# zb_pt4115_v1_2.net
KiCad netlist of a schematic drawn in EAGLE
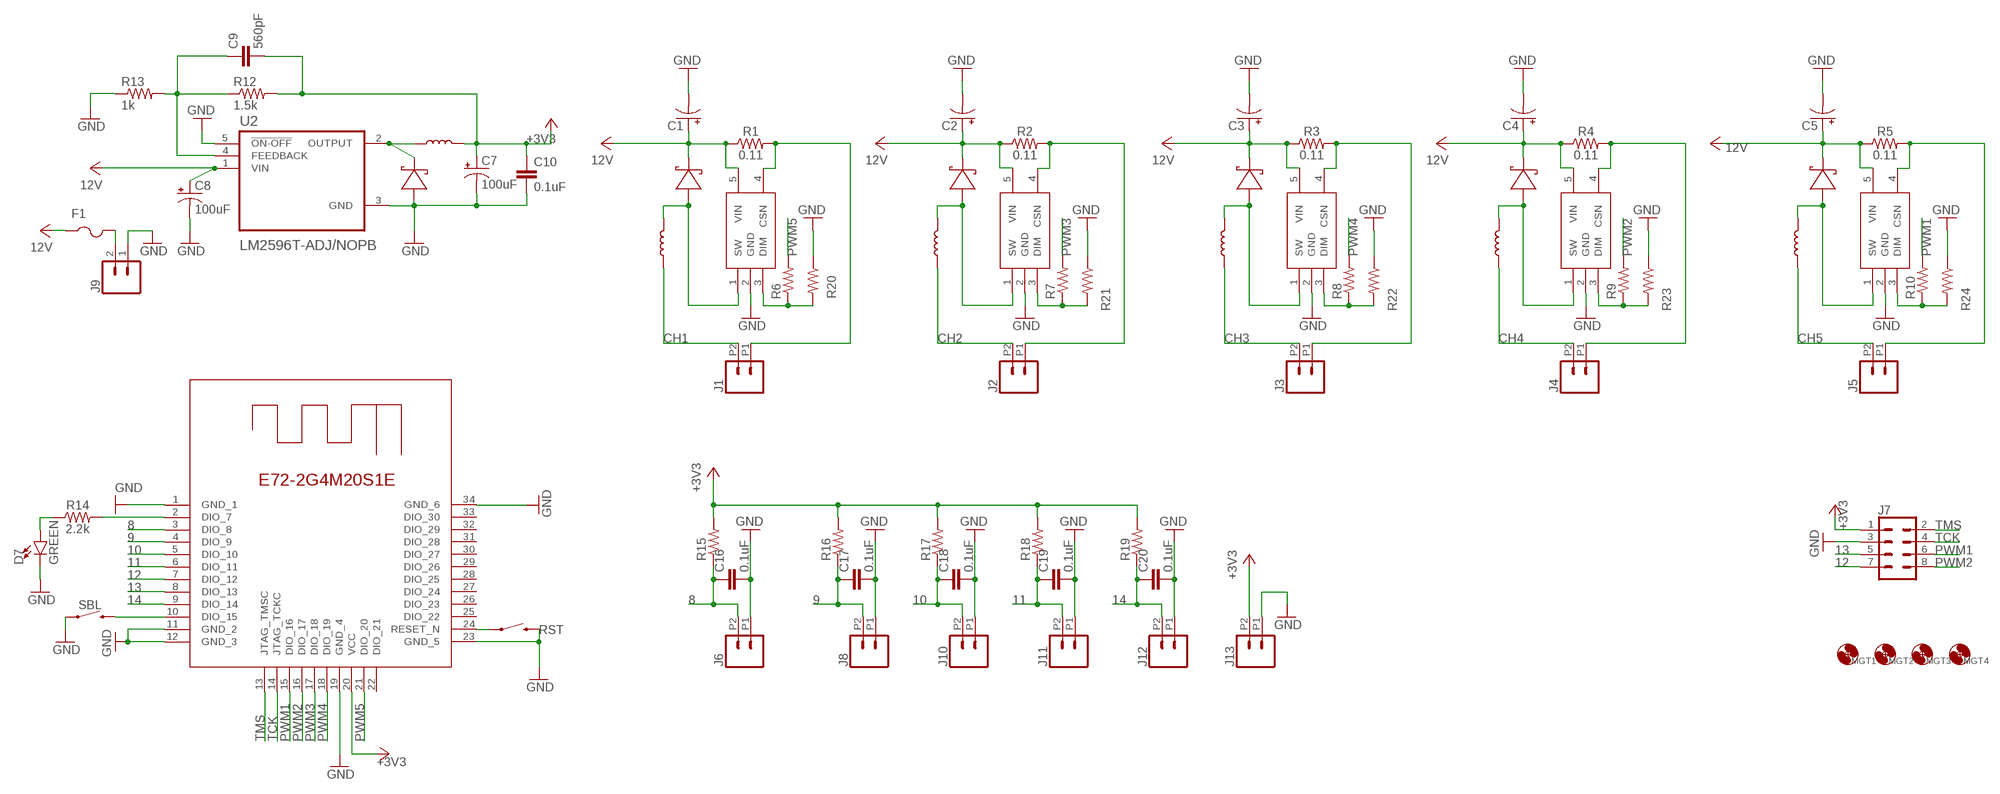
[diagram p0: schematic, sheet 1]

(export (version "E")
  (design (tool "Eeschema 10.0.6"))
  (components
    (comp (ref "C1")
      (value "100uF")
      (footprint "eagle-import:EIA7343")
      (libsource (lib "eagle-import") (part "100UF-POLAR-EIA7343-16V-10%(TANT)"))
    )
    (comp (ref "C2")
      (value "100uF")
      (footprint "eagle-import:EIA7343")
      (libsource (lib "eagle-import") (part "100UF-POLAR-EIA7343-16V-10%(TANT)"))
    )
    (comp (ref "C3")
      (value "100uF")
      (footprint "eagle-import:EIA7343")
      (libsource (lib "eagle-import") (part "100UF-POLAR-EIA7343-16V-10%(TANT)"))
    )
    (comp (ref "C4")
      (value "100uF")
      (footprint "eagle-import:EIA7343")
      (libsource (lib "eagle-import") (part "100UF-POLAR-EIA7343-16V-10%(TANT)"))
    )
    (comp (ref "C5")
      (value "100uF")
      (footprint "eagle-import:EIA7343")
      (libsource (lib "eagle-import") (part "100UF-POLAR-EIA7343-16V-10%(TANT)"))
    )
    (comp (ref "C7")
      (value "100uF")
      (footprint "eagle-import:PANASONIC_D")
      (libsource (lib "eagle-import") (part "SparkFun-Capacitors_510_100UF-POLAR-25V-20%(ELEC)"))
    )
    (comp (ref "C8")
      (value "100uF")
      (footprint "eagle-import:PANASONIC_D")
      (libsource (lib "eagle-import") (part "SparkFun-Capacitors_510_100UF-POLAR-25V-20%(ELEC)"))
    )
    (comp (ref "C9")
      (value "560pF")
      (footprint "eagle-import:0603")
      (libsource (lib "eagle-import") (part "560PF-0603-50V-5%"))
    )
    (comp (ref "C10")
      (value "0.1uF")
      (footprint "eagle-import:0603")
      (libsource (lib "eagle-import") (part "0.1UF-0603-25V-5%"))
    )
    (comp (ref "C16")
      (value "0.1uF")
      (footprint "eagle-import:0603")
      (libsource (lib "eagle-import") (part "0.1UF-0603-100V-10%"))
    )
    (comp (ref "C17")
      (value "0.1uF")
      (footprint "eagle-import:0603")
      (libsource (lib "eagle-import") (part "0.1UF-0603-100V-10%"))
    )
    (comp (ref "C18")
      (value "0.1uF")
      (footprint "eagle-import:0603")
      (libsource (lib "eagle-import") (part "0.1UF-0603-100V-10%"))
    )
    (comp (ref "C19")
      (value "0.1uF")
      (footprint "eagle-import:0603")
      (libsource (lib "eagle-import") (part "0.1UF-0603-100V-10%"))
    )
    (comp (ref "C20")
      (value "0.1uF")
      (footprint "eagle-import:0603")
      (libsource (lib "eagle-import") (part "0.1UF-0603-100V-10%"))
    )
    (comp (ref "D1")
      (value "SS18")
      (footprint "eagle-import:DIOM5227X270N")
      (fields (field (name "MOUSER_PART_NUMBER") "512-SS18"))
      (libsource (lib "eagle-import") (part "SS18"))
    )
    (comp (ref "D2")
      (value "SS18")
      (footprint "eagle-import:DIOM5227X270N")
      (fields (field (name "MOUSER_PART_NUMBER") "512-SS18"))
      (libsource (lib "eagle-import") (part "SS18"))
    )
    (comp (ref "D3")
      (value "SS18")
      (footprint "eagle-import:DIOM5227X270N")
      (fields (field (name "MOUSER_PART_NUMBER") "512-SS18"))
      (libsource (lib "eagle-import") (part "SS18"))
    )
    (comp (ref "D4")
      (value "SS18")
      (footprint "eagle-import:DIOM5227X270N")
      (fields (field (name "MOUSER_PART_NUMBER") "512-SS18"))
      (libsource (lib "eagle-import") (part "SS18"))
    )
    (comp (ref "D5")
      (value "SS18")
      (footprint "eagle-import:DIOM5227X270N")
      (fields (field (name "MOUSER_PART_NUMBER") "512-SS18"))
      (libsource (lib "eagle-import") (part "SS18"))
    )
    (comp (ref "D6")
      (value "SS18")
      (footprint "eagle-import:DIOM5227X270N")
      (fields (field (name "MOUSER_PART_NUMBER") "512-SS18"))
      (libsource (lib "eagle-import") (part "SS18"))
    )
    (comp (ref "D7")
      (value "GREEN")
      (footprint "eagle-import:LED-0603")
      (libsource (lib "eagle-import") (part "LED-GREEN0603"))
    )
    (comp (ref "F1")
      (value "PTCFUSE-1812")
      (footprint "eagle-import:1812")
      (libsource (lib "eagle-import") (part "PTCFUSE-1812"))
    )
    (comp (ref "IC1")
      (value "68uH")
      (footprint "eagle-import:INDPM102100X400N")
      (fields
        (field (name "MANUFACTURER_PART_NUMBER") "MSS1038-473MLB")
        (field (name "MOUSER_PART_NUMBER") "994-MSS1038-473MLB")
      )
      (libsource (lib "eagle-import") (part "MSS1038-473MLB"))
    )
    (comp (ref "IC2")
      (value "68uH")
      (footprint "eagle-import:INDPM102100X400N")
      (fields
        (field (name "MANUFACTURER_PART_NUMBER") "MSS1038-473MLB")
        (field (name "MOUSER_PART_NUMBER") "994-MSS1038-473MLB")
      )
      (libsource (lib "eagle-import") (part "MSS1038-473MLB"))
    )
    (comp (ref "IC3")
      (value "68uH")
      (footprint "eagle-import:INDPM102100X400N")
      (fields
        (field (name "MANUFACTURER_PART_NUMBER") "MSS1038-473MLB")
        (field (name "MOUSER_PART_NUMBER") "994-MSS1038-473MLB")
      )
      (libsource (lib "eagle-import") (part "MSS1038-473MLB"))
    )
    (comp (ref "IC4")
      (value "68uH")
      (footprint "eagle-import:INDPM102100X400N")
      (fields
        (field (name "MANUFACTURER_PART_NUMBER") "MSS1038-473MLB")
        (field (name "MOUSER_PART_NUMBER") "994-MSS1038-473MLB")
      )
      (libsource (lib "eagle-import") (part "MSS1038-473MLB"))
    )
    (comp (ref "IC5")
      (value "68uH")
      (footprint "eagle-import:INDPM102100X400N")
      (fields
        (field (name "MANUFACTURER_PART_NUMBER") "MSS1038-473MLB")
        (field (name "MOUSER_PART_NUMBER") "994-MSS1038-473MLB")
      )
      (libsource (lib "eagle-import") (part "MSS1038-473MLB"))
    )
    (comp (ref "IC6")
      (value "68uH")
      (footprint "eagle-import:INDPM102100X400N")
      (fields
        (field (name "MANUFACTURER_PART_NUMBER") "MSS1038-473MLB")
        (field (name "MOUSER_PART_NUMBER") "994-MSS1038-473MLB")
      )
      (libsource (lib "eagle-import") (part "MSS1038-473MLB"))
    )
    (comp (ref "J1")
      (value "CONN_022.54MM_SCREWTERM")
      (footprint "eagle-import:1X02_2.54_SCREWTERM")
      (libsource (lib "eagle-import") (part "CONN_022.54MM_SCREWTERM"))
    )
    (comp (ref "J2")
      (value "CONN_022.54MM_SCREWTERM")
      (footprint "eagle-import:1X02_2.54_SCREWTERM")
      (libsource (lib "eagle-import") (part "CONN_022.54MM_SCREWTERM"))
    )
    (comp (ref "J3")
      (value "CONN_022.54MM_SCREWTERM")
      (footprint "eagle-import:1X02_2.54_SCREWTERM")
      (libsource (lib "eagle-import") (part "CONN_022.54MM_SCREWTERM"))
    )
    (comp (ref "J4")
      (value "CONN_022.54MM_SCREWTERM")
      (footprint "eagle-import:1X02_2.54_SCREWTERM")
      (libsource (lib "eagle-import") (part "CONN_022.54MM_SCREWTERM"))
    )
    (comp (ref "J5")
      (value "CONN_022.54MM_SCREWTERM")
      (footprint "eagle-import:1X02_2.54_SCREWTERM")
      (libsource (lib "eagle-import") (part "CONN_022.54MM_SCREWTERM"))
    )
    (comp (ref "J6")
      (value "CONN_022.54MM_SCREWTERM")
      (footprint "eagle-import:1X02_2.54_SCREWTERM")
      (libsource (lib "eagle-import") (part "CONN_022.54MM_SCREWTERM"))
    )
    (comp (ref "J7")
      (value "CONN_04X2")
      (footprint "eagle-import:2X4")
      (libsource (lib "eagle-import") (part "CONN_04X2"))
    )
    (comp (ref "J8")
      (value "CONN_022.54MM_SCREWTERM")
      (footprint "eagle-import:1X02_2.54_SCREWTERM")
      (libsource (lib "eagle-import") (part "CONN_022.54MM_SCREWTERM"))
    )
    (comp (ref "J9")
      (value "CONN_025MM")
      (footprint "eagle-import:SCREWTERMINAL-5MM-2")
      (libsource (lib "eagle-import") (part "SparkFun-SEWPAD16_CONN_025MM"))
    )
    (comp (ref "J10")
      (value "CONN_022.54MM_SCREWTERM")
      (footprint "eagle-import:1X02_2.54_SCREWTERM")
      (libsource (lib "eagle-import") (part "CONN_022.54MM_SCREWTERM"))
    )
    (comp (ref "J11")
      (value "CONN_022.54MM_SCREWTERM")
      (footprint "eagle-import:1X02_2.54_SCREWTERM")
      (libsource (lib "eagle-import") (part "CONN_022.54MM_SCREWTERM"))
    )
    (comp (ref "J12")
      (value "CONN_022.54MM_SCREWTERM")
      (footprint "eagle-import:1X02_2.54_SCREWTERM")
      (libsource (lib "eagle-import") (part "CONN_022.54MM_SCREWTERM"))
    )
    (comp (ref "J13")
      (value "CONN_022.54MM_SCREWTERM")
      (footprint "eagle-import:1X02_2.54_SCREWTERM")
      (libsource (lib "eagle-import") (part "CONN_022.54MM_SCREWTERM"))
    )
    (comp (ref "MGT1")
      (value "MOUNT-HOLE3.0")
      (footprint "eagle-import:3,0")
      (libsource (lib "eagle-import") (part "MOUNT-HOLE3.0"))
    )
    (comp (ref "MGT2")
      (value "MOUNT-HOLE3.0")
      (footprint "eagle-import:3,0")
      (libsource (lib "eagle-import") (part "MOUNT-HOLE3.0"))
    )
    (comp (ref "MGT3")
      (value "MOUNT-HOLE3.0")
      (footprint "eagle-import:3,0")
      (libsource (lib "eagle-import") (part "MOUNT-HOLE3.0"))
    )
    (comp (ref "MGT4")
      (value "MOUNT-HOLE3.0")
      (footprint "eagle-import:3,0")
      (libsource (lib "eagle-import") (part "MOUNT-HOLE3.0"))
    )
    (comp (ref "R1")
      (value "0.11")
      (footprint "eagle-import:2010")
      (libsource (lib "eagle-import") (part "0.11OHM-2010-1/2W-1%"))
    )
    (comp (ref "R2")
      (value "0.11")
      (footprint "eagle-import:2010")
      (libsource (lib "eagle-import") (part "0.11OHM-2010-1/2W-1%"))
    )
    (comp (ref "R3")
      (value "0.11")
      (footprint "eagle-import:2010")
      (libsource (lib "eagle-import") (part "0.11OHM-2010-1/2W-1%"))
    )
    (comp (ref "R4")
      (value "0.11")
      (footprint "eagle-import:2010")
      (libsource (lib "eagle-import") (part "0.11OHM-2010-1/2W-1%"))
    )
    (comp (ref "R5")
      (value "0.11")
      (footprint "eagle-import:2010")
      (libsource (lib "eagle-import") (part "0.11OHM-2010-1/2W-1%"))
    )
    (comp (ref "R6")
      (value "100Ohm")
      (footprint "eagle-import:R0805")
      (libsource (lib "eagle-import") (part "R-US_R0805"))
    )
    (comp (ref "R7")
      (value "100Ohm")
      (footprint "eagle-import:R0805")
      (libsource (lib "eagle-import") (part "R-US_R0805"))
    )
    (comp (ref "R8")
      (value "100Ohm")
      (footprint "eagle-import:R0805")
      (libsource (lib "eagle-import") (part "R-US_R0805"))
    )
    (comp (ref "R9")
      (value "100Ohm")
      (footprint "eagle-import:R0805")
      (libsource (lib "eagle-import") (part "R-US_R0805"))
    )
    (comp (ref "R10")
      (value "100Ohm")
      (footprint "eagle-import:R0805")
      (libsource (lib "eagle-import") (part "R-US_R0805"))
    )
    (comp (ref "R12")
      (value "1.5k")
      (footprint "eagle-import:R0805")
      (libsource (lib "eagle-import") (part "R-US_R0805"))
    )
    (comp (ref "R13")
      (value "1k")
      (footprint "eagle-import:R0805")
      (libsource (lib "eagle-import") (part "R-US_R0805"))
    )
    (comp (ref "R14")
      (value "2.2k")
      (footprint "eagle-import:0603")
      (libsource (lib "eagle-import") (part "2.2KOHM-0603-1/10W-1%"))
    )
    (comp (ref "R15")
      (value "10k")
      (footprint "eagle-import:R0805")
      (libsource (lib "eagle-import") (part "R-US_R0805"))
    )
    (comp (ref "R16")
      (value "10k")
      (footprint "eagle-import:R0805")
      (libsource (lib "eagle-import") (part "R-US_R0805"))
    )
    (comp (ref "R17")
      (value "10k")
      (footprint "eagle-import:R0805")
      (libsource (lib "eagle-import") (part "R-US_R0805"))
    )
    (comp (ref "R18")
      (value "10k")
      (footprint "eagle-import:R0805")
      (libsource (lib "eagle-import") (part "R-US_R0805"))
    )
    (comp (ref "R19")
      (value "10k")
      (footprint "eagle-import:R0805")
      (libsource (lib "eagle-import") (part "R-US_R0805"))
    )
    (comp (ref "R20")
      (value "3k")
      (footprint "eagle-import:R0805")
      (libsource (lib "eagle-import") (part "R-US_R0805"))
    )
    (comp (ref "R21")
      (value "3k")
      (footprint "eagle-import:R0805")
      (libsource (lib "eagle-import") (part "R-US_R0805"))
    )
    (comp (ref "R22")
      (value "3k")
      (footprint "eagle-import:R0805")
      (libsource (lib "eagle-import") (part "R-US_R0805"))
    )
    (comp (ref "R23")
      (value "3k")
      (footprint "eagle-import:R0805")
      (libsource (lib "eagle-import") (part "R-US_R0805"))
    )
    (comp (ref "R24")
      (value "3k")
      (footprint "eagle-import:R0805")
      (libsource (lib "eagle-import") (part "R-US_R0805"))
    )
    (comp (ref "RST")
      (value "MOMENTARY-SWITCH-SPST-SMD-4.6X2.8MM")
      (footprint "eagle-import:TACTILE_SWITCH_SMD_4.6X2.8MM")
      (libsource (lib "eagle-import") (part "MOMENTARY-SWITCH-SPST-SMD-4.6X2.8MM"))
    )
    (comp (ref "SBL")
      (value "MOMENTARY-SWITCH-SPST-SMD-4.6X2.8MM")
      (footprint "eagle-import:TACTILE_SWITCH_SMD_4.6X2.8MM")
      (libsource (lib "eagle-import") (part "MOMENTARY-SWITCH-SPST-SMD-4.6X2.8MM"))
    )
    (comp (ref "U$1")
      (value "PT4115")
      (footprint "eagle-import:SOT-89-5")
      (fields (field (name "MF") "Pulse"))
      (libsource (lib "eagle-import") (part "PT4115"))
    )
    (comp (ref "U$2")
      (value "PT4115")
      (footprint "eagle-import:SOT-89-5")
      (fields (field (name "MF") "Pulse"))
      (libsource (lib "eagle-import") (part "PT4115"))
    )
    (comp (ref "U$3")
      (value "PT4115")
      (footprint "eagle-import:SOT-89-5")
      (fields (field (name "MF") "Pulse"))
      (libsource (lib "eagle-import") (part "PT4115"))
    )
    (comp (ref "U$4")
      (value "PT4115")
      (footprint "eagle-import:SOT-89-5")
      (fields (field (name "MF") "Pulse"))
      (libsource (lib "eagle-import") (part "PT4115"))
    )
    (comp (ref "U$5")
      (value "PT4115")
      (footprint "eagle-import:SOT-89-5")
      (fields (field (name "MF") "Pulse"))
      (libsource (lib "eagle-import") (part "PT4115"))
    )
    (comp (ref "U$6")
      (value "E72-2G4M20S1E")
      (footprint "eagle-import:E72-2G4M20S1E")
      (libsource (lib "eagle-import") (part "E72-2G4M20S1E"))
    )
    (comp (ref "U2")
      (value "LM2596T-ADJ/NOPB")
      (footprint "eagle-import:TO170P1016X470X2092-5")
      (fields (field (name "MF") "Texas Instruments"))
      (libsource (lib "eagle-import") (part "LM2596T-ADJ/NOPB"))
    )
  )
  (nets
    (net (code "1") (name "+3V3") (class "Default")
      (node (ref "C10") (pin "1") (pinfunction "1_1") (pintype "passive"))
      (node (ref "C7") (pin "+") (pinfunction "+_+") (pintype "passive"))
      (node (ref "C9") (pin "2") (pinfunction "2_2") (pintype "passive"))
      (node (ref "IC6") (pin "2") (pinfunction "2_2") (pintype "bidirectional"))
      (node (ref "J13") (pin "P2") (pinfunction "2_P2") (pintype "passive"))
      (node (ref "J7") (pin "1") (pinfunction "1_1") (pintype "passive"))
      (node (ref "R12") (pin "2") (pinfunction "2_2") (pintype "passive"))
      (node (ref "R15") (pin "2") (pinfunction "2_2") (pintype "passive"))
      (node (ref "R16") (pin "2") (pinfunction "2_2") (pintype "passive"))
      (node (ref "R17") (pin "2") (pinfunction "2_2") (pintype "passive"))
      (node (ref "R18") (pin "2") (pinfunction "2_2") (pintype "passive"))
      (node (ref "R19") (pin "2") (pinfunction "2_2") (pintype "passive"))
      (node (ref "U$6") (pin "20") (pinfunction "VCC_20") (pintype "bidirectional"))
    )
    (net (code "2") (name "/8") (class "Default")
      (node (ref "C16") (pin "1") (pinfunction "1_1") (pintype "passive"))
      (node (ref "J6") (pin "P2") (pinfunction "2_P2") (pintype "passive"))
      (node (ref "R15") (pin "1") (pinfunction "1_1") (pintype "passive"))
      (node (ref "U$6") (pin "3") (pinfunction "DIO_8_3") (pintype "bidirectional"))
    )
    (net (code "3") (name "/9") (class "Default")
      (node (ref "C17") (pin "1") (pinfunction "1_1") (pintype "passive"))
      (node (ref "J8") (pin "P2") (pinfunction "2_P2") (pintype "passive"))
      (node (ref "R16") (pin "1") (pinfunction "1_1") (pintype "passive"))
      (node (ref "U$6") (pin "4") (pinfunction "DIO_9_4") (pintype "bidirectional"))
    )
    (net (code "4") (name "/10") (class "Default")
      (node (ref "C18") (pin "1") (pinfunction "1_1") (pintype "passive"))
      (node (ref "J10") (pin "P2") (pinfunction "2_P2") (pintype "passive"))
      (node (ref "R17") (pin "1") (pinfunction "1_1") (pintype "passive"))
      (node (ref "U$6") (pin "5") (pinfunction "DIO_10_5") (pintype "bidirectional"))
    )
    (net (code "5") (name "/11") (class "Default")
      (node (ref "C19") (pin "1") (pinfunction "1_1") (pintype "passive"))
      (node (ref "J11") (pin "P2") (pinfunction "2_P2") (pintype "passive"))
      (node (ref "R18") (pin "1") (pinfunction "1_1") (pintype "passive"))
      (node (ref "U$6") (pin "6") (pinfunction "DIO_11_6") (pintype "bidirectional"))
    )
    (net (code "6") (name "/12") (class "Default")
      (node (ref "J7") (pin "7") (pinfunction "7_7") (pintype "passive"))
      (node (ref "U$6") (pin "7") (pinfunction "DIO_12_7") (pintype "bidirectional"))
    )
    (net (code "7") (name "/13") (class "Default")
      (node (ref "J7") (pin "5") (pinfunction "5_5") (pintype "passive"))
      (node (ref "U$6") (pin "8") (pinfunction "DIO_13_8") (pintype "bidirectional"))
    )
    (net (code "8") (name "/14") (class "Default")
      (node (ref "C20") (pin "1") (pinfunction "1_1") (pintype "passive"))
      (node (ref "J12") (pin "P2") (pinfunction "2_P2") (pintype "passive"))
      (node (ref "R19") (pin "1") (pinfunction "1_1") (pintype "passive"))
      (node (ref "U$6") (pin "9") (pinfunction "DIO_14_9") (pintype "bidirectional"))
    )
    (net (code "9") (name "/CH1") (class "Default")
      (node (ref "IC1") (pin "1") (pinfunction "1_1") (pintype "bidirectional"))
      (node (ref "J1") (pin "P2") (pinfunction "2_P2") (pintype "passive"))
    )
    (net (code "10") (name "/CH2") (class "Default")
      (node (ref "IC2") (pin "1") (pinfunction "1_1") (pintype "bidirectional"))
      (node (ref "J2") (pin "P2") (pinfunction "2_P2") (pintype "passive"))
    )
    (net (code "11") (name "/CH3") (class "Default")
      (node (ref "IC3") (pin "1") (pinfunction "1_1") (pintype "bidirectional"))
      (node (ref "J3") (pin "P2") (pinfunction "2_P2") (pintype "passive"))
    )
    (net (code "12") (name "/CH4") (class "Default")
      (node (ref "IC4") (pin "1") (pinfunction "1_1") (pintype "bidirectional"))
      (node (ref "J4") (pin "P2") (pinfunction "2_P2") (pintype "passive"))
    )
    (net (code "13") (name "/CH5") (class "Default")
      (node (ref "IC5") (pin "1") (pinfunction "1_1") (pintype "bidirectional"))
      (node (ref "J5") (pin "P2") (pinfunction "2_P2") (pintype "passive"))
    )
    (net (code "14") (name "/PWM1") (class "Default")
      (node (ref "J7") (pin "6") (pinfunction "6_6") (pintype "passive"))
      (node (ref "R10") (pin "2") (pinfunction "2_2") (pintype "passive"))
      (node (ref "U$6") (pin "15") (pinfunction "DIO_16_15") (pintype "bidirectional"))
    )
    (net (code "15") (name "/PWM2") (class "Default")
      (node (ref "J7") (pin "8") (pinfunction "8_8") (pintype "passive"))
      (node (ref "R9") (pin "2") (pinfunction "2_2") (pintype "passive"))
      (node (ref "U$6") (pin "16") (pinfunction "DIO_17_16") (pintype "bidirectional"))
    )
    (net (code "16") (name "/PWM3") (class "Default")
      (node (ref "R7") (pin "2") (pinfunction "2_2") (pintype "passive"))
      (node (ref "U$6") (pin "17") (pinfunction "DIO_18_17") (pintype "bidirectional"))
    )
    (net (code "17") (name "/PWM4") (class "Default")
      (node (ref "R8") (pin "2") (pinfunction "2_2") (pintype "passive"))
      (node (ref "U$6") (pin "18") (pinfunction "DIO_19_18") (pintype "bidirectional"))
    )
    (net (code "18") (name "/PWM5") (class "Default")
      (node (ref "R6") (pin "2") (pinfunction "2_2") (pintype "passive"))
      (node (ref "U$6") (pin "21") (pinfunction "DIO_20_21") (pintype "bidirectional"))
    )
    (net (code "19") (name "/TCK") (class "Default")
      (node (ref "J7") (pin "4") (pinfunction "4_4") (pintype "passive"))
      (node (ref "U$6") (pin "14") (pinfunction "JTAG_TCKC_14") (pintype "bidirectional"))
    )
    (net (code "20") (name "/TMS") (class "Default")
      (node (ref "J7") (pin "2") (pinfunction "2_2") (pintype "passive"))
      (node (ref "U$6") (pin "13") (pinfunction "JTAG_TMSC_13") (pintype "bidirectional"))
    )
    (net (code "21") (name "12V") (class "Default")
      (node (ref "C1") (pin "A") (pinfunction "+_A") (pintype "passive"))
      (node (ref "C2") (pin "A") (pinfunction "+_A") (pintype "passive"))
      (node (ref "C3") (pin "A") (pinfunction "+_A") (pintype "passive"))
      (node (ref "C4") (pin "A") (pinfunction "+_A") (pintype "passive"))
      (node (ref "C5") (pin "A") (pinfunction "+_A") (pintype "passive"))
      (node (ref "C8") (pin "+") (pinfunction "+_+") (pintype "passive"))
      (node (ref "D1") (pin "1") (pinfunction "K_1") (pintype "bidirectional"))
      (node (ref "D2") (pin "1") (pinfunction "K_1") (pintype "bidirectional"))
      (node (ref "D3") (pin "1") (pinfunction "K_1") (pintype "bidirectional"))
      (node (ref "D4") (pin "1") (pinfunction "K_1") (pintype "bidirectional"))
      (node (ref "D5") (pin "1") (pinfunction "K_1") (pintype "bidirectional"))
      (node (ref "F1") (pin "1") (pinfunction "1_1") (pintype "passive"))
      (node (ref "F1") (pin "2") (pinfunction "2_2") (pintype "passive"))
      (node (ref "J9") (pin "2") (pinfunction "2_2") (pintype "passive"))
      (node (ref "R1") (pin "1") (pinfunction "1_1") (pintype "passive"))
      (node (ref "R2") (pin "1") (pinfunction "1_1") (pintype "passive"))
      (node (ref "R3") (pin "1") (pinfunction "1_1") (pintype "passive"))
      (node (ref "R4") (pin "1") (pinfunction "1_1") (pintype "passive"))
      (node (ref "R5") (pin "1") (pinfunction "1_1") (pintype "passive"))
      (node (ref "U$1") (pin "5") (pinfunction "VIN_5") (pintype "bidirectional"))
      (node (ref "U$2") (pin "5") (pinfunction "VIN_5") (pintype "bidirectional"))
      (node (ref "U$3") (pin "5") (pinfunction "VIN_5") (pintype "bidirectional"))
      (node (ref "U$4") (pin "5") (pinfunction "VIN_5") (pintype "bidirectional"))
      (node (ref "U$5") (pin "5") (pinfunction "VIN_5") (pintype "bidirectional"))
      (node (ref "U2") (pin "1") (pinfunction "VIN_1") (pintype "input"))
    )
    (net (code "22") (name "GND") (class "Default")
      (node (ref "C1") (pin "C") (pinfunction "-_C") (pintype "passive"))
      (node (ref "C10") (pin "2") (pinfunction "2_2") (pintype "passive"))
      (node (ref "C16") (pin "2") (pinfunction "2_2") (pintype "passive"))
      (node (ref "C17") (pin "2") (pinfunction "2_2") (pintype "passive"))
      (node (ref "C18") (pin "2") (pinfunction "2_2") (pintype "passive"))
      (node (ref "C19") (pin "2") (pinfunction "2_2") (pintype "passive"))
      (node (ref "C2") (pin "C") (pinfunction "-_C") (pintype "passive"))
      (node (ref "C20") (pin "2") (pinfunction "2_2") (pintype "passive"))
      (node (ref "C3") (pin "C") (pinfunction "-_C") (pintype "passive"))
      (node (ref "C4") (pin "C") (pinfunction "-_C") (pintype "passive"))
      (node (ref "C5") (pin "C") (pinfunction "-_C") (pintype "passive"))
      (node (ref "C7") (pin "-") (pinfunction "-_-") (pintype "passive"))
      (node (ref "C8") (pin "-") (pinfunction "-_-") (pintype "passive"))
      (node (ref "D6") (pin "2") (pinfunction "A_2") (pintype "bidirectional"))
      (node (ref "D7") (pin "C") (pinfunction "C_C") (pintype "passive"))
      (node (ref "J10") (pin "P1") (pinfunction "1_P1") (pintype "passive"))
      (node (ref "J11") (pin "P1") (pinfunction "1_P1") (pintype "passive"))
      (node (ref "J12") (pin "P1") (pinfunction "1_P1") (pintype "passive"))
      (node (ref "J13") (pin "P1") (pinfunction "1_P1") (pintype "passive"))
      (node (ref "J6") (pin "P1") (pinfunction "1_P1") (pintype "passive"))
      (node (ref "J7") (pin "3") (pinfunction "3_3") (pintype "passive"))
      (node (ref "J8") (pin "P1") (pinfunction "1_P1") (pintype "passive"))
      (node (ref "J9") (pin "1") (pinfunction "1_1") (pintype "passive"))
      (node (ref "R13") (pin "1") (pinfunction "1_1") (pintype "passive"))
      (node (ref "R20") (pin "1") (pinfunction "1_1") (pintype "passive"))
      (node (ref "R21") (pin "1") (pinfunction "1_1") (pintype "passive"))
      (node (ref "R22") (pin "1") (pinfunction "1_1") (pintype "passive"))
      (node (ref "R23") (pin "1") (pinfunction "1_1") (pintype "passive"))
      (node (ref "R24") (pin "1") (pinfunction "1_1") (pintype "passive"))
      (node (ref "RST") (pin "3") (pinfunction "2_3") (pintype "passive"))
      (node (ref "RST") (pin "4") (pinfunction "2_4") (pintype "passive"))
      (node (ref "SBL") (pin "1") (pinfunction "1_1") (pintype "passive"))
      (node (ref "SBL") (pin "2") (pinfunction "1_2") (pintype "passive"))
      (node (ref "U$1") (pin "2") (pinfunction "GND_2") (pintype "bidirectional"))
      (node (ref "U$2") (pin "2") (pinfunction "GND_2") (pintype "bidirectional"))
      (node (ref "U$3") (pin "2") (pinfunction "GND_2") (pintype "bidirectional"))
      (node (ref "U$4") (pin "2") (pinfunction "GND_2") (pintype "bidirectional"))
      (node (ref "U$5") (pin "2") (pinfunction "GND_2") (pintype "bidirectional"))
      (node (ref "U$6") (pin "1") (pinfunction "GND_1_1") (pintype "bidirectional"))
      (node (ref "U$6") (pin "11") (pinfunction "GND_2_11") (pintype "bidirectional"))
      (node (ref "U$6") (pin "12") (pinfunction "GND_3_12") (pintype "bidirectional"))
      (node (ref "U$6") (pin "19") (pinfunction "GND_4_19") (pintype "bidirectional"))
      (node (ref "U$6") (pin "23") (pinfunction "GND_5_23") (pintype "bidirectional"))
      (node (ref "U$6") (pin "34") (pinfunction "GND_6_34") (pintype "bidirectional"))
      (node (ref "U2") (pin "3") (pinfunction "GND_3") (pintype "power_in"))
      (node (ref "U2") (pin "5") (pinfunction "~{ON-OFF}_5") (pintype "input"))
    )
    (net (code "23") (name "Net-(D1-A)") (class "Default")
      (node (ref "D1") (pin "2") (pinfunction "A_2") (pintype "bidirectional"))
      (node (ref "IC1") (pin "2") (pinfunction "2_2") (pintype "bidirectional"))
      (node (ref "U$1") (pin "1") (pinfunction "SW_1") (pintype "bidirectional"))
    )
    (net (code "24") (name "Net-(D2-A)") (class "Default")
      (node (ref "D2") (pin "2") (pinfunction "A_2") (pintype "bidirectional"))
      (node (ref "IC2") (pin "2") (pinfunction "2_2") (pintype "bidirectional"))
      (node (ref "U$2") (pin "1") (pinfunction "SW_1") (pintype "bidirectional"))
    )
    (net (code "25") (name "Net-(D3-A)") (class "Default")
      (node (ref "D3") (pin "2") (pinfunction "A_2") (pintype "bidirectional"))
      (node (ref "IC3") (pin "2") (pinfunction "2_2") (pintype "bidirectional"))
      (node (ref "U$3") (pin "1") (pinfunction "SW_1") (pintype "bidirectional"))
    )
    (net (code "26") (name "Net-(D4-A)") (class "Default")
      (node (ref "D4") (pin "2") (pinfunction "A_2") (pintype "bidirectional"))
      (node (ref "IC4") (pin "2") (pinfunction "2_2") (pintype "bidirectional"))
      (node (ref "U$4") (pin "1") (pinfunction "SW_1") (pintype "bidirectional"))
    )
    (net (code "27") (name "Net-(D5-A)") (class "Default")
      (node (ref "D5") (pin "2") (pinfunction "A_2") (pintype "bidirectional"))
      (node (ref "IC5") (pin "2") (pinfunction "2_2") (pintype "bidirectional"))
      (node (ref "U$5") (pin "1") (pinfunction "SW_1") (pintype "bidirectional"))
    )
    (net (code "28") (name "Net-(D6-K)") (class "Default")
      (node (ref "D6") (pin "1") (pinfunction "K_1") (pintype "bidirectional"))
      (node (ref "IC6") (pin "1") (pinfunction "1_1") (pintype "bidirectional"))
      (node (ref "U2") (pin "2") (pinfunction "OUTPUT_2") (pintype "output"))
    )
    (net (code "29") (name "Net-(D7-PadA)") (class "Default")
      (node (ref "D7") (pin "A") (pinfunction "A_A") (pintype "passive"))
      (node (ref "R14") (pin "1") (pinfunction "1_1") (pintype "passive"))
    )
    (net (code "30") (name "Net-(J1-1)") (class "Default")
      (node (ref "J1") (pin "P1") (pinfunction "1_P1") (pintype "passive"))
      (node (ref "R1") (pin "2") (pinfunction "2_2") (pintype "passive"))
      (node (ref "U$1") (pin "4") (pinfunction "CSN_4") (pintype "bidirectional"))
    )
    (net (code "31") (name "Net-(J2-1)") (class "Default")
      (node (ref "J2") (pin "P1") (pinfunction "1_P1") (pintype "passive"))
      (node (ref "R2") (pin "2") (pinfunction "2_2") (pintype "passive"))
      (node (ref "U$2") (pin "4") (pinfunction "CSN_4") (pintype "bidirectional"))
    )
    (net (code "32") (name "Net-(J3-1)") (class "Default")
      (node (ref "J3") (pin "P1") (pinfunction "1_P1") (pintype "passive"))
      (node (ref "R3") (pin "2") (pinfunction "2_2") (pintype "passive"))
      (node (ref "U$3") (pin "4") (pinfunction "CSN_4") (pintype "bidirectional"))
    )
    (net (code "33") (name "Net-(J4-1)") (class "Default")
      (node (ref "J4") (pin "P1") (pinfunction "1_P1") (pintype "passive"))
      (node (ref "R4") (pin "2") (pinfunction "2_2") (pintype "passive"))
      (node (ref "U$4") (pin "4") (pinfunction "CSN_4") (pintype "bidirectional"))
    )
    (net (code "34") (name "Net-(J5-1)") (class "Default")
      (node (ref "J5") (pin "P1") (pinfunction "1_P1") (pintype "passive"))
      (node (ref "R5") (pin "2") (pinfunction "2_2") (pintype "passive"))
      (node (ref "U$5") (pin "4") (pinfunction "CSN_4") (pintype "bidirectional"))
    )
    (net (code "35") (name "Net-(U$1-DIM)") (class "Default")
      (node (ref "R20") (pin "2") (pinfunction "2_2") (pintype "passive"))
      (node (ref "R6") (pin "1") (pinfunction "1_1") (pintype "passive"))
      (node (ref "U$1") (pin "3") (pinfunction "DIM_3") (pintype "bidirectional"))
    )
    (net (code "36") (name "Net-(U$2-DIM)") (class "Default")
      (node (ref "R21") (pin "2") (pinfunction "2_2") (pintype "passive"))
      (node (ref "R7") (pin "1") (pinfunction "1_1") (pintype "passive"))
      (node (ref "U$2") (pin "3") (pinfunction "DIM_3") (pintype "bidirectional"))
    )
    (net (code "37") (name "Net-(U$3-DIM)") (class "Default")
      (node (ref "R22") (pin "2") (pinfunction "2_2") (pintype "passive"))
      (node (ref "R8") (pin "1") (pinfunction "1_1") (pintype "passive"))
      (node (ref "U$3") (pin "3") (pinfunction "DIM_3") (pintype "bidirectional"))
    )
    (net (code "38") (name "Net-(U$4-DIM)") (class "Default")
      (node (ref "R23") (pin "2") (pinfunction "2_2") (pintype "passive"))
      (node (ref "R9") (pin "1") (pinfunction "1_1") (pintype "passive"))
      (node (ref "U$4") (pin "3") (pinfunction "DIM_3") (pintype "bidirectional"))
    )
    (net (code "39") (name "Net-(U$5-DIM)") (class "Default")
      (node (ref "R10") (pin "1") (pinfunction "1_1") (pintype "passive"))
      (node (ref "R24") (pin "2") (pinfunction "2_2") (pintype "passive"))
      (node (ref "U$5") (pin "3") (pinfunction "DIM_3") (pintype "bidirectional"))
    )
    (net (code "40") (name "Net-(U$6-DIO_7)") (class "Default")
      (node (ref "R14") (pin "2") (pinfunction "2_2") (pintype "passive"))
      (node (ref "U$6") (pin "2") (pinfunction "DIO_7_2") (pintype "bidirectional"))
    )
    (net (code "41") (name "Net-(U$6-DIO_15)") (class "Default")
      (node (ref "SBL") (pin "3") (pinfunction "2_3") (pintype "passive"))
      (node (ref "SBL") (pin "4") (pinfunction "2_4") (pintype "passive"))
      (node (ref "U$6") (pin "10") (pinfunction "DIO_15_10") (pintype "bidirectional"))
    )
    (net (code "42") (name "Net-(U$6-RESET_N)") (class "Default")
      (node (ref "RST") (pin "1") (pinfunction "1_1") (pintype "passive"))
      (node (ref "RST") (pin "2") (pinfunction "1_2") (pintype "passive"))
      (node (ref "U$6") (pin "24") (pinfunction "RESET_N_24") (pintype "bidirectional"))
    )
    (net (code "43") (name "Net-(U2-FEEDBACK)") (class "Default")
      (node (ref "C9") (pin "1") (pinfunction "1_1") (pintype "passive"))
      (node (ref "R12") (pin "1") (pinfunction "1_1") (pintype "passive"))
      (node (ref "R13") (pin "2") (pinfunction "2_2") (pintype "passive"))
      (node (ref "U2") (pin "4") (pinfunction "FEEDBACK_4") (pintype "input"))
    )
    (net (code "44") (name "unconnected-(U$6-DIO_21-Pad22)") (class "Default")
      (node (ref "U$6") (pin "22") (pinfunction "DIO_21_22") (pintype "bidirectional"))
    )
    (net (code "45") (name "unconnected-(U$6-DIO_22-Pad25)") (class "Default")
      (node (ref "U$6") (pin "25") (pinfunction "DIO_22_25") (pintype "bidirectional"))
    )
    (net (code "46") (name "unconnected-(U$6-DIO_23-Pad26)") (class "Default")
      (node (ref "U$6") (pin "26") (pinfunction "DIO_23_26") (pintype "bidirectional"))
    )
    (net (code "47") (name "unconnected-(U$6-DIO_24-Pad27)") (class "Default")
      (node (ref "U$6") (pin "27") (pinfunction "DIO_24_27") (pintype "bidirectional"))
    )
    (net (code "48") (name "unconnected-(U$6-DIO_25-Pad28)") (class "Default")
      (node (ref "U$6") (pin "28") (pinfunction "DIO_25_28") (pintype "bidirectional"))
    )
    (net (code "49") (name "unconnected-(U$6-DIO_26-Pad29)") (class "Default")
      (node (ref "U$6") (pin "29") (pinfunction "DIO_26_29") (pintype "bidirectional"))
    )
    (net (code "50") (name "unconnected-(U$6-DIO_27-Pad30)") (class "Default")
      (node (ref "U$6") (pin "30") (pinfunction "DIO_27_30") (pintype "bidirectional"))
    )
    (net (code "51") (name "unconnected-(U$6-DIO_28-Pad31)") (class "Default")
      (node (ref "U$6") (pin "31") (pinfunction "DIO_28_31") (pintype "bidirectional"))
    )
    (net (code "52") (name "unconnected-(U$6-DIO_29-Pad32)") (class "Default")
      (node (ref "U$6") (pin "32") (pinfunction "DIO_29_32") (pintype "bidirectional"))
    )
    (net (code "53") (name "unconnected-(U$6-DIO_30-Pad33)") (class "Default")
      (node (ref "U$6") (pin "33") (pinfunction "DIO_30_33") (pintype "bidirectional"))
    )
  )
)
